# Gastroscopy-CutController_Accelerometer.net
KiCad netlist of a schematic drawn in Altium Designer
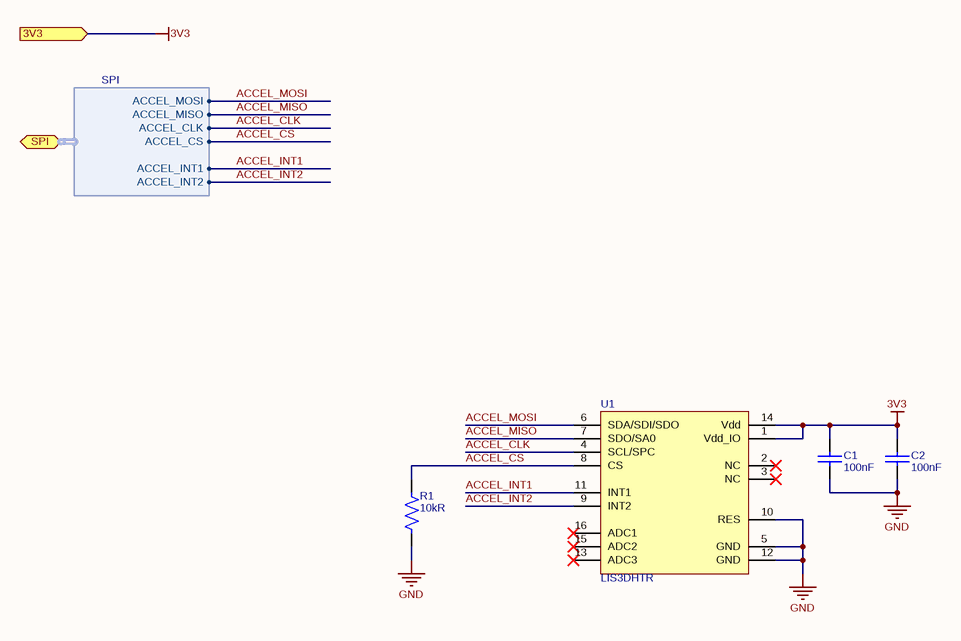
[diagram p0: Gastroscopy-CutController_Accelerometer.SchDoc]

(export (version "E")
  (design (tool "Eeschema 10.0.6"))
  (components
    (comp (ref "C1")
      (value "100nF")
      (footprint "CAP_0603")
      (description "CAP CER 0.1UF 50V X7R 0603")
      (fields (field (name "TOLERANCE") "10%"))
      (libsource (lib "Gastroscopy-Controller") (part "CL10B104KB8NNNL"))
    )
    (comp (ref "C2")
      (value "100nF")
      (footprint "CAP_0603")
      (description "CAP CER 0.1UF 50V X7R 0603")
      (fields (field (name "TOLERANCE") "10%"))
      (libsource (lib "Gastroscopy-Controller") (part "CL10B104KB8NNNL"))
    )
    (comp (ref "R1")
      (value "10kR")
      (footprint "RES_0603")
      (description "RES 10K OHM 1% 1/10W 0603")
      (fields (field (name "TOLERANCE") "1%"))
      (libsource (lib "Gastroscopy-Controller") (part "RC0603FR-0710KL"))
    )
    (comp (ref "U1")
      (value "LIS3DHTR")
      (footprint "LIS3DHTR")
      (description "ACCEL 2-16G I2C/SPI 16LGA")
      (libsource (lib "Gastroscopy-Controller") (part "LIS3DHTR"))
    )
  )
  (nets
    (net (code "2") (name "/ACCEL_CLK") (class "Default")
      (node (ref "U1") (pin "4") (pinfunction "SCL/SPC_4") (pintype "passive"))
    )
    (net (code "3") (name "/ACCEL_CS") (class "Default")
      (node (ref "R1") (pin "1") (pinfunction "1_1") (pintype "passive"))
      (node (ref "U1") (pin "8") (pinfunction "CS_8") (pintype "passive"))
    )
    (net (code "4") (name "/ACCEL_INT1") (class "Default")
      (node (ref "U1") (pin "11") (pinfunction "INT1_11") (pintype "passive"))
    )
    (net (code "5") (name "/ACCEL_INT2") (class "Default")
      (node (ref "U1") (pin "9") (pinfunction "INT2_9") (pintype "passive"))
    )
    (net (code "6") (name "/ACCEL_MISO") (class "Default")
      (node (ref "U1") (pin "7") (pinfunction "SDO/SA0_7") (pintype "passive"))
    )
    (net (code "7") (name "/ACCEL_MOSI") (class "Default")
      (node (ref "U1") (pin "6") (pinfunction "SDA/SDI/SDO_6") (pintype "passive"))
    )
    (net (code "9") (name "3V3") (class "Default")
      (node (ref "C1") (pin "1") (pinfunction "1_1") (pintype "passive"))
      (node (ref "C2") (pin "1") (pinfunction "1_1") (pintype "passive"))
      (node (ref "U1") (pin "1") (pinfunction "Vdd_IO_1") (pintype "passive"))
      (node (ref "U1") (pin "14") (pinfunction "Vdd_14") (pintype "passive"))
    )
    (net (code "10") (name "GND") (class "Default")
      (node (ref "C1") (pin "2") (pinfunction "2_2") (pintype "passive"))
      (node (ref "C2") (pin "2") (pinfunction "2_2") (pintype "passive"))
      (node (ref "R1") (pin "2") (pinfunction "2_2") (pintype "passive"))
      (node (ref "U1") (pin "10") (pinfunction "RES_10") (pintype "passive"))
      (node (ref "U1") (pin "12") (pinfunction "GND_12") (pintype "passive"))
      (node (ref "U1") (pin "5") (pinfunction "GND_5") (pintype "passive"))
    )
    (net (code "11") (name "unconnected-(U1-ADC1-Pad16)") (class "Default")
      (node (ref "U1") (pin "16") (pinfunction "ADC1_16") (pintype "passive+no_connect"))
    )
    (net (code "12") (name "unconnected-(U1-ADC2-Pad15)") (class "Default")
      (node (ref "U1") (pin "15") (pinfunction "ADC2_15") (pintype "passive+no_connect"))
    )
    (net (code "13") (name "unconnected-(U1-ADC3-Pad13)") (class "Default")
      (node (ref "U1") (pin "13") (pinfunction "ADC3_13") (pintype "passive+no_connect"))
    )
    (net (code "14") (name "unconnected-(U1-NC-Pad2)") (class "Default")
      (node (ref "U1") (pin "2") (pinfunction "NC_2") (pintype "passive+no_connect"))
    )
    (net (code "15") (name "unconnected-(U1-NC-Pad3)") (class "Default")
      (node (ref "U1") (pin "3") (pinfunction "NC_3") (pintype "passive+no_connect"))
    )
  )
)
